# PowerBoard.net
KiCad netlist of a schematic drawn in Altium Designer
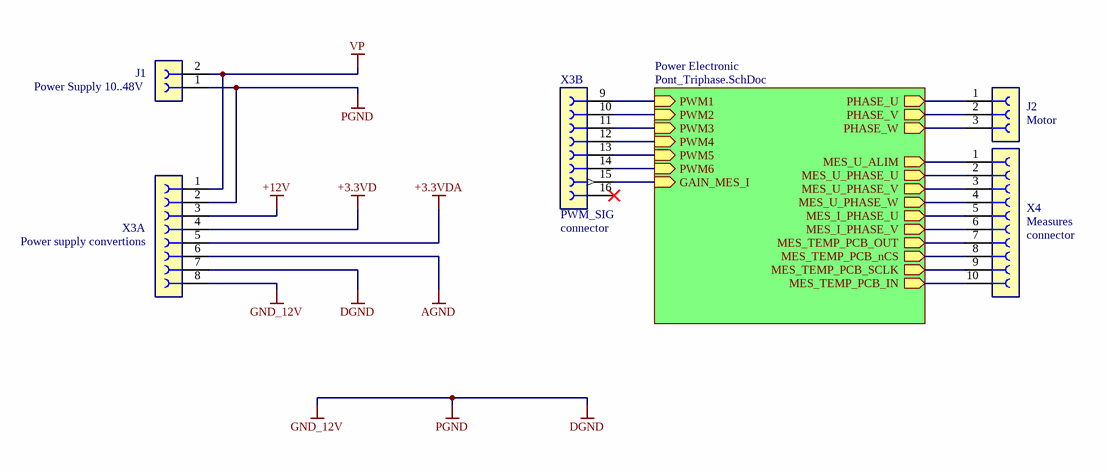
[diagram p0: PowerBoard.SchDoc]

(export (version "E")
  (design (tool "Eeschema 10.0.6"))
  (components
    (comp (ref "J1")
      (value "CONNECT 2pos 90°")
      (footprint "PowerBoard:CONNECT2PIN")
      (fields (field (name "USE") "Power Supply 10..48V"))
      (libsource (lib "PowerBoard") (part "CONNECT 2pos 90° 3.81mm"))
    )
    (comp (ref "J2")
      (value "CONNECT 3pos 90°")
      (footprint "PowerBoard:CONNECT3PIN")
      (fields (field (name "USE") "Motor"))
      (libsource (lib "PowerBoard") (part "CONNECT 3pos 90° 3.81mm"))
    )
    (comp (ref "X3")
      (value "CONNECT SMD 16pos 2row 180°")
      (footprint "PowerBoard:62301621021")
      (fields (field (name "USE") "Power supply convertions") (field (name "SYSTEM") "connector"))
      (libsource (lib "") (part "CONNECT SMD 16pos 180° 1.27mm 2row_1"))
    )
    (comp (ref "X4")
      (value "CONNECT SMD 10pos 2row 180°")
      (footprint "PowerBoard:62301021021")
      (fields (field (name "USE") "Measures") (field (name "SYSTEM") "connector"))
      (libsource (lib "PowerBoard") (part "CONNECT SMD 10pos 180° 1.27mm 2row"))
    )
  )
  (nets
    (net (code "1") (name "+3.3VD") (class "Default")
      (node (ref "X3") (pin "4") (pinfunction "4_4") (pintype "passive"))
    )
    (net (code "2") (name "+3.3VDA") (class "Default")
      (node (ref "X3") (pin "5") (pinfunction "5_5") (pintype "passive"))
    )
    (net (code "3") (name "+12V") (class "Default")
      (node (ref "X3") (pin "3") (pinfunction "3_3") (pintype "passive"))
    )
    (net (code "4") (name "/GAIN_MES_I") (class "Default")
      (node (ref "X3") (pin "15") (pinfunction "15_15") (pintype "output"))
    )
    (net (code "5") (name "/MES_I_PHASE_U") (class "Default")
      (node (ref "X4") (pin "5") (pinfunction "5_5") (pintype "passive"))
    )
    (net (code "6") (name "/MES_I_PHASE_V") (class "Default")
      (node (ref "X4") (pin "6") (pinfunction "6_6") (pintype "passive"))
    )
    (net (code "7") (name "/MES_TEMP_PCB_IN") (class "Default")
      (node (ref "X4") (pin "10") (pinfunction "10_10") (pintype "passive"))
    )
    (net (code "8") (name "/MES_TEMP_PCB_OUT") (class "Default")
      (node (ref "X4") (pin "7") (pinfunction "7_7") (pintype "passive"))
    )
    (net (code "9") (name "/MES_TEMP_PCB_SCLK") (class "Default")
      (node (ref "X4") (pin "9") (pinfunction "9_9") (pintype "passive"))
    )
    (net (code "10") (name "/MES_TEMP_PCB_nCS") (class "Default")
      (node (ref "X4") (pin "8") (pinfunction "8_8") (pintype "passive"))
    )
    (net (code "11") (name "/MES_U_ALIM") (class "Default")
      (node (ref "X4") (pin "1") (pinfunction "1_1") (pintype "passive"))
    )
    (net (code "12") (name "/MES_U_PHASE_U") (class "Default")
      (node (ref "X4") (pin "2") (pinfunction "2_2") (pintype "passive"))
    )
    (net (code "13") (name "/MES_U_PHASE_V") (class "Default")
      (node (ref "X4") (pin "3") (pinfunction "3_3") (pintype "passive"))
    )
    (net (code "14") (name "/MES_U_PHASE_W") (class "Default")
      (node (ref "X4") (pin "4") (pinfunction "4_4") (pintype "passive"))
    )
    (net (code "15") (name "/PHASE_U") (class "Default")
      (node (ref "J2") (pin "1") (pinfunction "1_1") (pintype "passive"))
    )
    (net (code "16") (name "/PHASE_V") (class "Default")
      (node (ref "J2") (pin "2") (pinfunction "2_2") (pintype "passive"))
    )
    (net (code "17") (name "/PHASE_W") (class "Default")
      (node (ref "J2") (pin "3") (pinfunction "3_3") (pintype "passive"))
    )
    (net (code "18") (name "/PWM1") (class "Default")
      (node (ref "X3") (pin "9") (pinfunction "9_9") (pintype "passive"))
    )
    (net (code "19") (name "/PWM2") (class "Default")
      (node (ref "X3") (pin "10") (pinfunction "10_10") (pintype "passive"))
    )
    (net (code "20") (name "/PWM3") (class "Default")
      (node (ref "X3") (pin "11") (pinfunction "11_11") (pintype "passive"))
    )
    (net (code "21") (name "/PWM4") (class "Default")
      (node (ref "X3") (pin "12") (pinfunction "12_12") (pintype "passive"))
    )
    (net (code "22") (name "/PWM5") (class "Default")
      (node (ref "X3") (pin "13") (pinfunction "13_13") (pintype "passive"))
    )
    (net (code "23") (name "/PWM6") (class "Default")
      (node (ref "X3") (pin "14") (pinfunction "14_14") (pintype "passive"))
    )
    (net (code "24") (name "AGND") (class "Default")
      (node (ref "X3") (pin "6") (pinfunction "6_6") (pintype "passive"))
    )
    (net (code "25") (name "DGND") (class "Default")
      (node (ref "J1") (pin "1") (pinfunction "1_1") (pintype "passive"))
      (node (ref "X3") (pin "2") (pinfunction "2_2") (pintype "passive"))
      (node (ref "X3") (pin "7") (pinfunction "7_7") (pintype "passive"))
      (node (ref "X3") (pin "8") (pinfunction "8_8") (pintype "passive"))
    )
    (net (code "26") (name "VP") (class "Default")
      (node (ref "J1") (pin "2") (pinfunction "2_2") (pintype "passive"))
      (node (ref "X3") (pin "1") (pinfunction "1_1") (pintype "passive"))
    )
    (net (code "27") (name "unconnected-(X3-Pad16)") (class "Default")
      (node (ref "X3") (pin "16") (pinfunction "16_16") (pintype "passive+no_connect"))
    )
  )
)
